# CC1101RGPR.net
KiCad netlist of a schematic drawn in Altium Designer
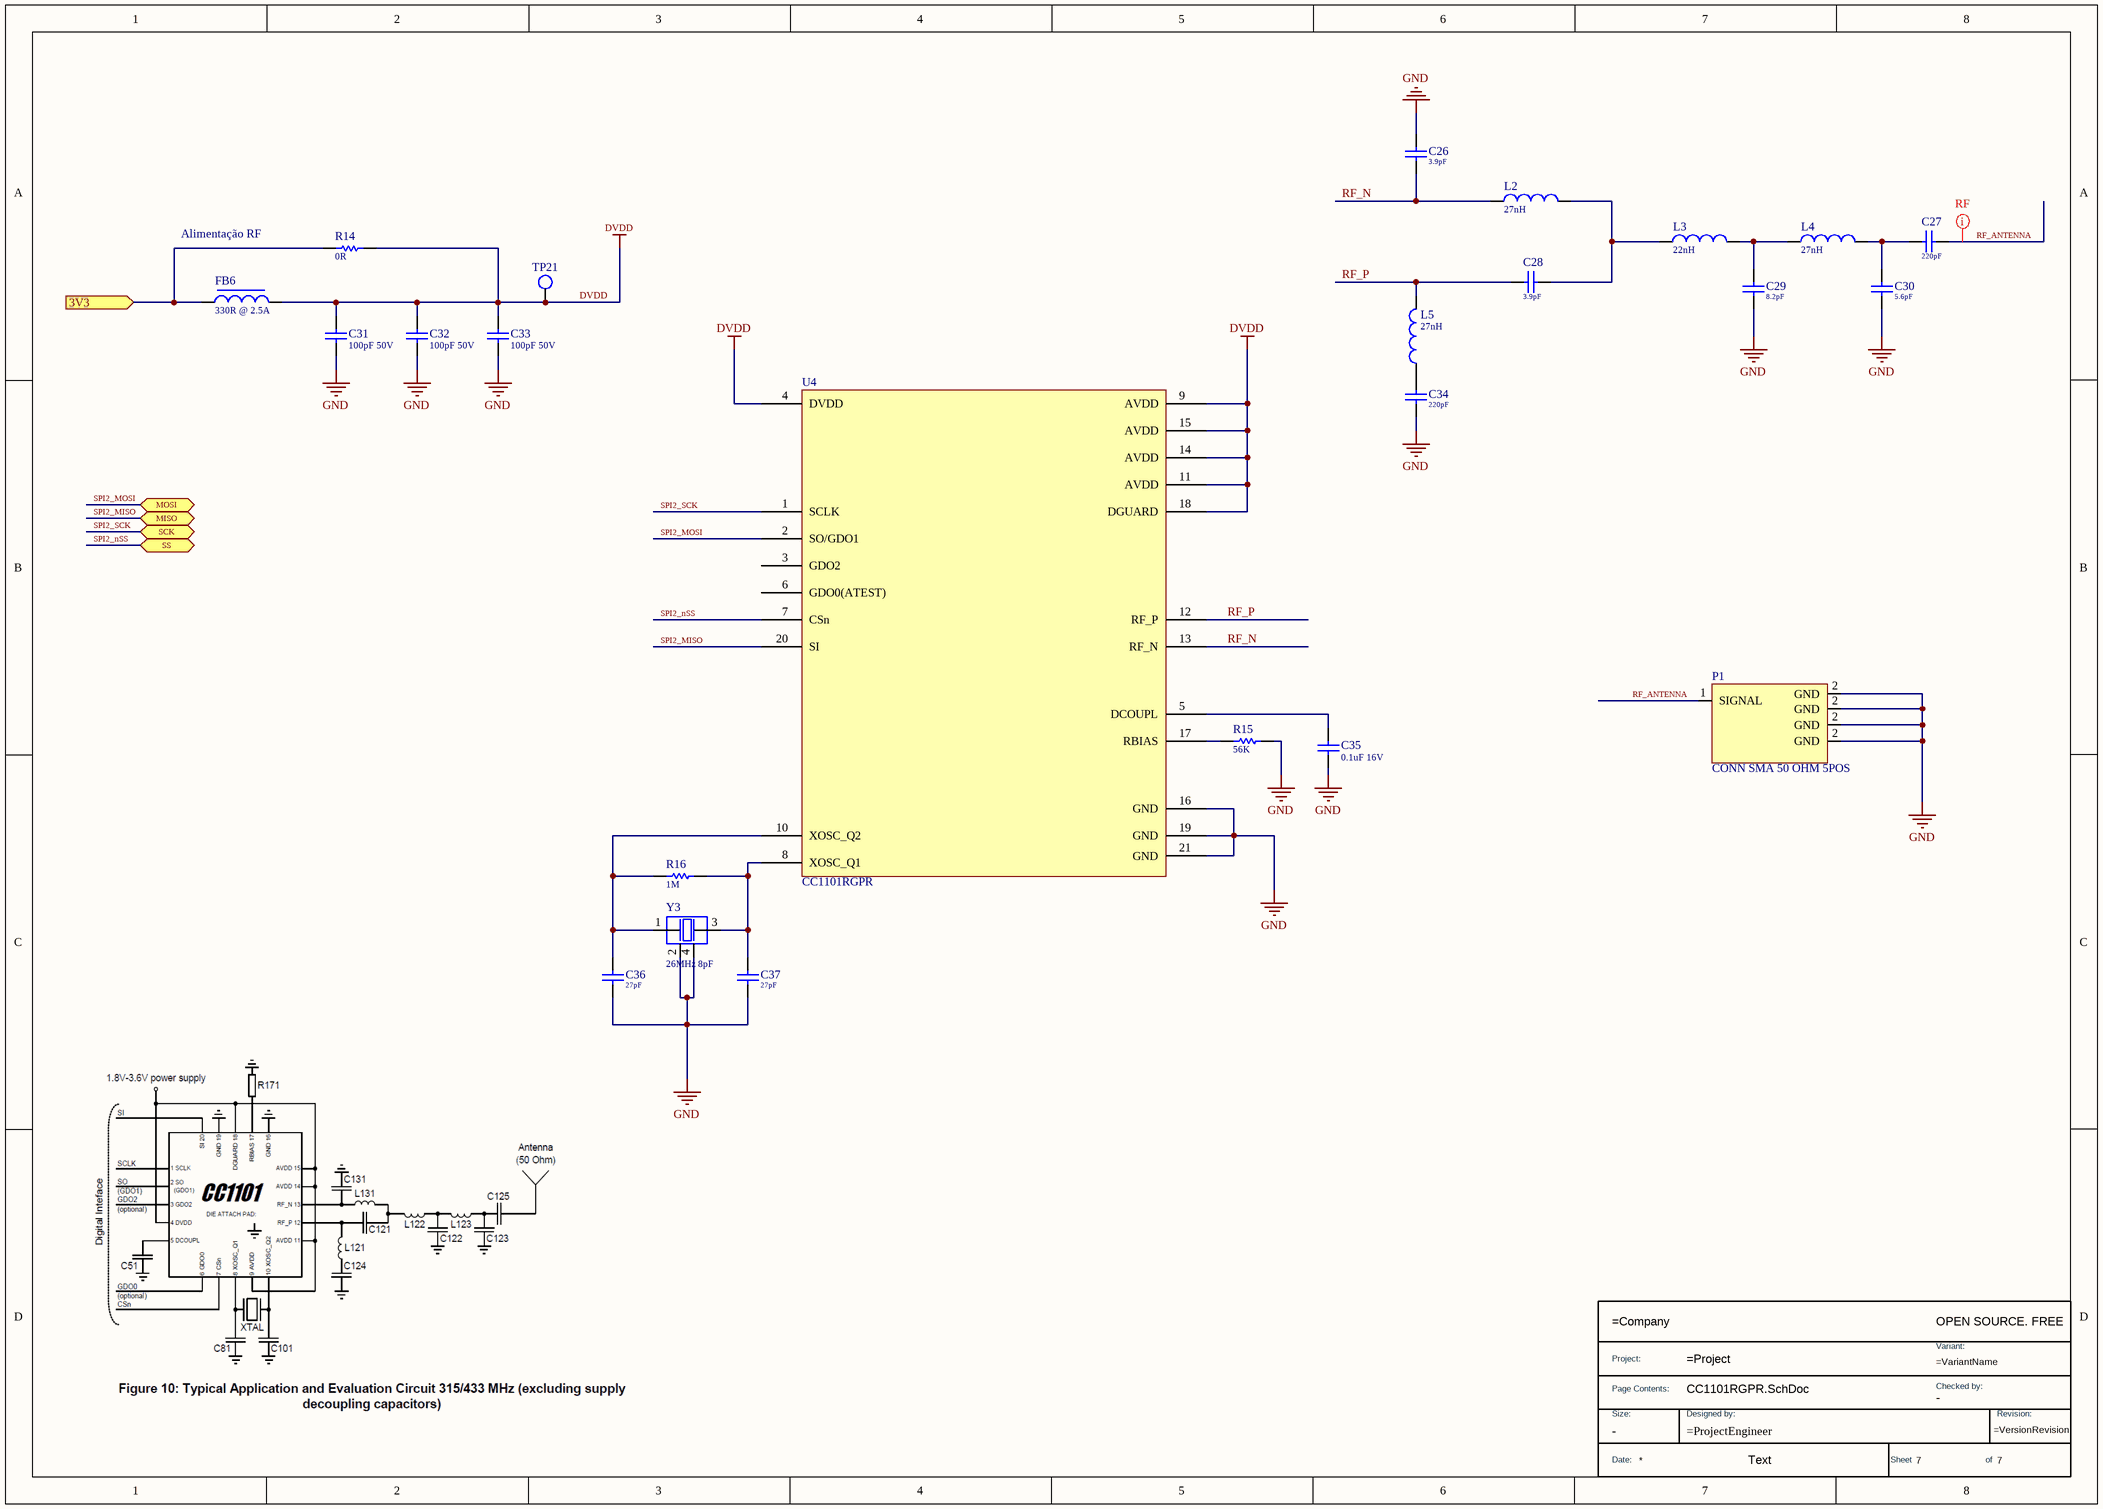
[diagram p0: CC1101RGPR.SchDoc]

(export (version "E")
  (design (tool "Eeschema 10.0.6"))
  (components
    (comp (ref "C26")
      (value "GJM1555C1H3R9WB01D")
      (footprint "CAP 0402")
      (description "CAP CER 3.9PF 50V C0G/NP0 0402")
      (fields (field (name "MANUFACTURER") "Murata Electronics") (field (name "VALOR") "3.9pF"))
      (libsource (lib "OBDH_Ed02") (part "GJM1555C1H3R9WB01D"))
    )
    (comp (ref "C27")
      (value "GRM155R71H221JA01D")
      (footprint "CAP 0402")
      (description "CAP CER 220PF 50V X7R 0402")
      (fields (field (name "MANUFACTURER") "Murata Electronics") (field (name "VALOR") "220pF"))
      (libsource (lib "OBDH_Ed02") (part "GRM155R71H221JA01D"))
    )
    (comp (ref "C28")
      (value "GJM1555C1H3R9WB01D")
      (footprint "CAP 0402")
      (description "CAP CER 3.9PF 50V C0G/NP0 0402")
      (fields (field (name "MANUFACTURER") "Murata Electronics") (field (name "VALOR") "3.9pF"))
      (libsource (lib "OBDH_Ed02") (part "GJM1555C1H3R9WB01D"))
    )
    (comp (ref "C29")
      (value "GCM1555C1H8R2CA16D")
      (footprint "CAP 0402")
      (description "CAP CER 8.2PF 50V C0G/NP0 0402")
      (fields (field (name "MANUFACTURER") "Murata Electronics") (field (name "VALOR") "8.2pF"))
      (libsource (lib "OBDH_Ed02") (part "GCM1555C1H8R2CA16D"))
    )
    (comp (ref "C30")
      (value "GRM1555C1H5R6CA01D")
      (footprint "CAP 0402")
      (description "CAP CER 5.6PF 50V C0G/NP0 0402")
      (fields (field (name "MANUFACTURER") "Murata Electronics") (field (name "VALOR") "5.6pF"))
      (libsource (lib "OBDH_Ed02") (part "GRM1555C1H5R6CA01D"))
    )
    (comp (ref "C31")
      (value "CC0805JRNPO9BN101")
      (footprint "CAP_0805")
      (description "CAP CER 100PF 50V C0G/NPO 0805")
      (fields (field (name "MANUFACTURER") "YAGEO") (field (name "VALOR") "100pF 50V"))
      (libsource (lib "OBDH_Ed02") (part "CC0805JRNPO9BN101"))
    )
    (comp (ref "C32")
      (value "CC0805JRNPO9BN101")
      (footprint "CAP_0805")
      (description "CAP CER 100PF 50V C0G/NPO 0805")
      (fields (field (name "MANUFACTURER") "YAGEO") (field (name "VALOR") "100pF 50V"))
      (libsource (lib "OBDH_Ed02") (part "CC0805JRNPO9BN101"))
    )
    (comp (ref "C33")
      (value "CC0805JRNPO9BN101")
      (footprint "CAP_0805")
      (description "CAP CER 100PF 50V C0G/NPO 0805")
      (fields (field (name "MANUFACTURER") "YAGEO") (field (name "VALOR") "100pF 50V"))
      (libsource (lib "OBDH_Ed02") (part "CC0805JRNPO9BN101"))
    )
    (comp (ref "C34")
      (value "GRM155R71H221JA01D")
      (footprint "CAP 0402")
      (description "CAP CER 220PF 50V X7R 0402")
      (fields (field (name "MANUFACTURER") "Murata Electronics") (field (name "VALOR") "220pF"))
      (libsource (lib "OBDH_Ed02") (part "GRM155R71H221JA01D"))
    )
    (comp (ref "C35")
      (value "CL05B104KO5NNNC")
      (footprint "CAP_0805")
      (description "CAP CER 0.1UF 16V X5R 0805")
      (fields (field (name "MANUFACTURER") "Samsung Electro-Mechanics") (field (name "VALOR") "0.1uF 16V"))
      (libsource (lib "OBDH_Ed02") (part "CL05B104KO5NNNC"))
    )
    (comp (ref "C36")
      (value "GCM1555C1H270JA16D")
      (footprint "CAP 0402")
      (description "CAP CER 27PF 50V C0G/NP0 0402")
      (fields (field (name "MANUFACTURER") "Murata Electronics") (field (name "VALOR") "27pF"))
      (libsource (lib "OBDH_Ed02") (part "GCM1555C1H270JA16D"))
    )
    (comp (ref "C37")
      (value "GCM1555C1H270JA16D")
      (footprint "CAP 0402")
      (description "CAP CER 27PF 50V C0G/NP0 0402")
      (fields (field (name "MANUFACTURER") "Murata Electronics") (field (name "VALOR") "27pF"))
      (libsource (lib "OBDH_Ed02") (part "GCM1555C1H270JA16D"))
    )
    (comp (ref "FB6")
      (value "MPZ2012S331AT000")
      (footprint "IND_0805")
      (description "FERRITE BEAD 330 OHM 0805 1LN")
      (fields (field (name "MANUFACTURER") "TDK Corporation") (field (name "VALOR") "330R @ 2.5A"))
      (libsource (lib "OBDH_Ed02") (part "MPZ2012S331AT000"))
    )
    (comp (ref "L2")
      (value "27nH")
      (footprint "IND 0402")
      (description "FIXED IND 27NH 350MA 460MOHM SMD")
      (fields
        (field (name "MANUFACTURER") "Murata Electronics")
        (field (name "MANUFACTURER PART NUMBER") "LQG15HS27NH02D")
      )
      (libsource (lib "OBDH_Ed02") (part "LQG15HS27NH02D"))
    )
    (comp (ref "L3")
      (value "22nH")
      (footprint "IND 0402")
      (description "FIXED IND 22NH 350MA 580MOHM SMD")
      (fields
        (field (name "MANUFACTURER") "Murata Electronics")
        (field (name "MANUFACTURER PART NUMBER") "LQG15HN22NH02D")
      )
      (libsource (lib "OBDH_Ed02") (part "LQG15HN22NH02D"))
    )
    (comp (ref "L4")
      (value "27nH")
      (footprint "IND 0402")
      (description "FIXED IND 27NH 350MA 460MOHM SMD")
      (fields
        (field (name "MANUFACTURER") "Murata Electronics")
        (field (name "MANUFACTURER PART NUMBER") "LQG15HS27NH02D")
      )
      (libsource (lib "OBDH_Ed02") (part "LQG15HS27NH02D"))
    )
    (comp (ref "L5")
      (value "27nH")
      (footprint "IND 0402")
      (description "FIXED IND 27NH 350MA 460MOHM SMD")
      (fields
        (field (name "MANUFACTURER") "Murata Electronics")
        (field (name "MANUFACTURER PART NUMBER") "LQG15HS27NH02D")
      )
      (libsource (lib "OBDH_Ed02") (part "LQG15HS27NH02D"))
    )
    (comp (ref "P1")
      (value "CONN SMA 50 OHM 5POS")
      (footprint "CONN PTH SMA JACK CONSMA002-L-G")
      (description "CONN SMA JACK R/A 50OHM PCB")
      (libsource (lib "OBDH_Ed02") (part "CONN SMA 50 OHM 5POS"))
    )
    (comp (ref "R14")
      (value "RC0805JR-070RL")
      (footprint "RES_0805")
      (description "RES 0 OHM JUMPER 1/8W 0805")
      (fields (field (name "MANUFACTURER") "YAGEO") (field (name "VALOR") "0R"))
      (libsource (lib "OBDH_Ed02") (part "RC0805JR-070RL"))
    )
    (comp (ref "R15")
      (value "**CRCW080562K0JNEA")
      (footprint "RES_0805")
      (description "RES SMD 56K OHM 5% 1/8W 0805")
      (fields
        (field (name "MANUFACTURER") "YAGEO")
        (field (name "MANUFACTURER PART NUMBER") "CRCW080562K0JNEA")
        (field (name "VALOR") "56K")
      )
      (libsource (lib "OBDH_Ed02") (part "**CRCW080562K0JNEA"))
    )
    (comp (ref "R16")
      (value "CRCW08051M00JNEA")
      (footprint "RES 0402")
      (description "RES SMD 1M OHM 5% 1/8W 0805")
      (fields (field (name "MANUFACTURER") "Vishay Intertech") (field (name "VALOR") "1M"))
      (libsource (lib "OBDH_Ed02") (part "CRCW08051M00JNEA"))
    )
    (comp (ref "TP21")
      (value "TEST_POINT_1.5MM")
      (footprint "TESTPOINT_1.5MM")
      (description "TEST_POINT")
      (libsource (lib "OBDH_Ed02") (part "TEST_POINT_1.5MM"))
    )
    (comp (ref "U4")
      (value "CC1101RGPR")
      (footprint "QLP-4x4")
      (description "IC RF TXRX ISM<1GHZ 20VFQFN")
      (libsource (lib "OBDH_Ed02") (part "CC1101RGPR"))
    )
    (comp (ref "Y3")
      (value "NX3225SA-26MHZ")
      (footprint "Crystal-4SMD")
      (description "CRYSTAL 26.0000MHZ 10PF SMD")
      (fields (field (name "MANUFACTURER") "NDK America, Inc.") (field (name "VALOR") "26MHz 8pF"))
      (libsource (lib "OBDH_Ed02") (part "NX3225SA-26MHZ"))
    )
  )
  (nets
    (net (code "1") (name "/3V3") (class "Default")
      (node (ref "FB6") (pin "1") (pinfunction "1_1") (pintype "passive"))
      (node (ref "R14") (pin "1") (pinfunction "1_1") (pintype "passive"))
    )
    (net (code "2") (name "/RF_ANTENNA") (class "Default")
      (node (ref "C27") (pin "2") (pinfunction "2_2") (pintype "passive"))
      (node (ref "P1") (pin "1") (pinfunction "SIGNAL_1") (pintype "passive"))
    )
    (net (code "3") (name "/RF_N") (class "Default")
      (node (ref "C26") (pin "1") (pinfunction "1_1") (pintype "passive"))
      (node (ref "L2") (pin "1") (pinfunction "1_1") (pintype "passive"))
      (node (ref "U4") (pin "13") (pinfunction "RF_N_13") (pintype "passive"))
    )
    (net (code "4") (name "/RF_P") (class "Default")
      (node (ref "C28") (pin "1") (pinfunction "1_1") (pintype "passive"))
      (node (ref "L5") (pin "2") (pinfunction "2_2") (pintype "passive"))
      (node (ref "U4") (pin "12") (pinfunction "RF_P_12") (pintype "passive"))
    )
    (net (code "5") (name "/SPI2_MISO") (class "Default")
      (node (ref "U4") (pin "20") (pinfunction "SI_20") (pintype "passive"))
    )
    (net (code "6") (name "/SPI2_MOSI") (class "Default")
      (node (ref "U4") (pin "2") (pinfunction "SO/GDO1_2") (pintype "passive"))
    )
    (net (code "7") (name "/SPI2_SCK") (class "Default")
      (node (ref "U4") (pin "1") (pinfunction "SCLK_1") (pintype "passive"))
    )
    (net (code "8") (name "/SPI2_nSS") (class "Default")
      (node (ref "U4") (pin "7") (pinfunction "CSn_7") (pintype "passive"))
    )
    (net (code "9") (name "DVDD") (class "Default")
      (node (ref "C31") (pin "2") (pinfunction "2_2") (pintype "passive"))
      (node (ref "C32") (pin "2") (pinfunction "2_2") (pintype "passive"))
      (node (ref "C33") (pin "2") (pinfunction "2_2") (pintype "passive"))
      (node (ref "FB6") (pin "2") (pinfunction "2_2") (pintype "passive"))
      (node (ref "R14") (pin "2") (pinfunction "2_2") (pintype "passive"))
      (node (ref "TP21") (pin "1") (pinfunction "1_1") (pintype "passive"))
      (node (ref "U4") (pin "11") (pinfunction "AVDD_11") (pintype "passive"))
      (node (ref "U4") (pin "14") (pinfunction "AVDD_14") (pintype "passive"))
      (node (ref "U4") (pin "15") (pinfunction "AVDD_15") (pintype "passive"))
      (node (ref "U4") (pin "18") (pinfunction "DGUARD_18") (pintype "passive"))
      (node (ref "U4") (pin "4") (pinfunction "DVDD_4") (pintype "passive"))
      (node (ref "U4") (pin "9") (pinfunction "AVDD_9") (pintype "passive"))
    )
    (net (code "10") (name "GND") (class "Default")
      (node (ref "C26") (pin "2") (pinfunction "2_2") (pintype "passive"))
      (node (ref "C29") (pin "2") (pinfunction "2_2") (pintype "passive"))
      (node (ref "C30") (pin "1") (pinfunction "1_1") (pintype "passive"))
      (node (ref "C31") (pin "1") (pinfunction "1_1") (pintype "passive"))
      (node (ref "C32") (pin "1") (pinfunction "1_1") (pintype "passive"))
      (node (ref "C33") (pin "1") (pinfunction "1_1") (pintype "passive"))
      (node (ref "C34") (pin "1") (pinfunction "1_1") (pintype "passive"))
      (node (ref "C35") (pin "1") (pinfunction "1_1") (pintype "passive"))
      (node (ref "C36") (pin "1") (pinfunction "1_1") (pintype "passive"))
      (node (ref "C37") (pin "1") (pinfunction "1_1") (pintype "passive"))
      (node (ref "P1") (pin "2") (pinfunction "GND_2") (pintype "power_in"))
      (node (ref "R15") (pin "2") (pinfunction "2_2") (pintype "passive"))
      (node (ref "U4") (pin "16") (pinfunction "GND_16") (pintype "passive"))
      (node (ref "U4") (pin "19") (pinfunction "GND_19") (pintype "passive"))
      (node (ref "U4") (pin "21") (pinfunction "GND_21") (pintype "passive"))
      (node (ref "Y3") (pin "2") (pinfunction "2_2") (pintype "passive"))
      (node (ref "Y3") (pin "4") (pinfunction "4_4") (pintype "passive"))
    )
    (net (code "11") (name "Net-(C27-Pad1)") (class "Default")
      (node (ref "C27") (pin "1") (pinfunction "1_1") (pintype "passive"))
      (node (ref "C30") (pin "2") (pinfunction "2_2") (pintype "passive"))
      (node (ref "L4") (pin "2") (pinfunction "2_2") (pintype "passive"))
    )
    (net (code "12") (name "Net-(C28-Pad2)") (class "Default")
      (node (ref "C28") (pin "2") (pinfunction "2_2") (pintype "passive"))
      (node (ref "L2") (pin "2") (pinfunction "2_2") (pintype "passive"))
      (node (ref "L3") (pin "1") (pinfunction "1_1") (pintype "passive"))
    )
    (net (code "13") (name "Net-(C29-Pad1)") (class "Default")
      (node (ref "C29") (pin "1") (pinfunction "1_1") (pintype "passive"))
      (node (ref "L3") (pin "2") (pinfunction "2_2") (pintype "passive"))
      (node (ref "L4") (pin "1") (pinfunction "1_1") (pintype "passive"))
    )
    (net (code "14") (name "Net-(C34-Pad2)") (class "Default")
      (node (ref "C34") (pin "2") (pinfunction "2_2") (pintype "passive"))
      (node (ref "L5") (pin "1") (pinfunction "1_1") (pintype "passive"))
    )
    (net (code "15") (name "Net-(U4-DCOUPL)") (class "Default")
      (node (ref "C35") (pin "2") (pinfunction "2_2") (pintype "passive"))
      (node (ref "U4") (pin "5") (pinfunction "DCOUPL_5") (pintype "passive"))
    )
    (net (code "16") (name "Net-(U4-RBIAS)") (class "Default")
      (node (ref "R15") (pin "1") (pinfunction "1_1") (pintype "passive"))
      (node (ref "U4") (pin "17") (pinfunction "RBIAS_17") (pintype "passive"))
    )
    (net (code "17") (name "Net-(U4-XOSC_Q1)") (class "Default")
      (node (ref "C37") (pin "2") (pinfunction "2_2") (pintype "passive"))
      (node (ref "R16") (pin "2") (pinfunction "2_2") (pintype "passive"))
      (node (ref "U4") (pin "8") (pinfunction "XOSC_Q1_8") (pintype "passive"))
      (node (ref "Y3") (pin "3") (pinfunction "3_3") (pintype "passive"))
    )
    (net (code "18") (name "Net-(U4-XOSC_Q2)") (class "Default")
      (node (ref "C36") (pin "2") (pinfunction "2_2") (pintype "passive"))
      (node (ref "R16") (pin "1") (pinfunction "1_1") (pintype "passive"))
      (node (ref "U4") (pin "10") (pinfunction "XOSC_Q2_10") (pintype "passive"))
      (node (ref "Y3") (pin "1") (pinfunction "1_1") (pintype "passive"))
    )
    (net (code "19") (name "unconnected-(U4-GDO0(ATEST)-Pad6)") (class "Default")
      (node (ref "U4") (pin "6") (pinfunction "GDO0(ATEST)_6") (pintype "passive"))
    )
    (net (code "20") (name "unconnected-(U4-GDO2-Pad3)") (class "Default")
      (node (ref "U4") (pin "3") (pinfunction "GDO2_3") (pintype "passive"))
    )
  )
)
